# tdlf_08_15_2021_server_top.net
KiCad netlist of a schematic drawn in EAGLE
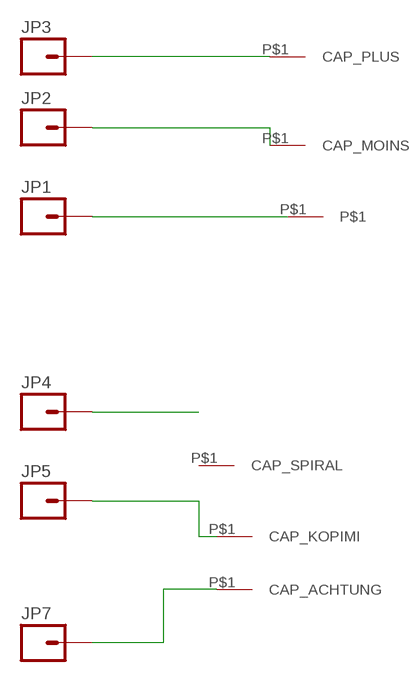
[diagram p0: schematic, sheet 1]

(export (version "E")
  (design (tool "Eeschema 10.0.6"))
  (components
    (comp (ref "CAP_MUSH")
      (value "MUSH")
      (footprint "eagle-import:TDLF_CAP_02")
      (libsource (lib "eagle-import") (part "TDLF_CAP_02"))
    )
    (comp (ref "CAP_PLUS")
      (value "TDLF_CAP_PLUS")
      (footprint "eagle-import:TDLF_CAP_PLUS")
      (libsource (lib "eagle-import") (part "TDLF_CAP_PLUS"))
    )
    (comp (ref "JP1")
      (value "M01SMD")
      (footprint "eagle-import:LUXEON-PAD")
      (libsource (lib "eagle-import") (part "M01SMD"))
    )
    (comp (ref "JP2")
      (value "M01SMD")
      (footprint "eagle-import:LUXEON-PAD")
      (libsource (lib "eagle-import") (part "M01SMD"))
    )
    (comp (ref "JP3")
      (value "M01SMD")
      (footprint "eagle-import:LUXEON-PAD")
      (libsource (lib "eagle-import") (part "M01SMD"))
    )
    (comp (ref "JP4")
      (value "M01SMD")
      (footprint "eagle-import:LUXEON-PAD")
      (libsource (lib "eagle-import") (part "M01SMD"))
    )
    (comp (ref "JP5")
      (value "M01SMD")
      (footprint "eagle-import:LUXEON-PAD")
      (libsource (lib "eagle-import") (part "M01SMD"))
    )
    (comp (ref "JP7")
      (value "M01SMD")
      (footprint "eagle-import:LUXEON-PAD")
      (libsource (lib "eagle-import") (part "M01SMD"))
    )
    (comp (ref "U$1")
      (value "TDLF_CAP_MOINS")
      (footprint "eagle-import:TDLF_CAP_MOINS")
      (libsource (lib "eagle-import") (part "TDLF_CAP_MOINS"))
    )
    (comp (ref "U$2")
      (value "TDLF_CAP_SPIRAL")
      (footprint "eagle-import:TDLF_CAP_SPIRAL")
      (libsource (lib "eagle-import") (part "TDLF_CAP_SPIRAL"))
    )
    (comp (ref "U$3")
      (value "TDLF_CAP_KOPIMI")
      (footprint "eagle-import:TDLF_CAP_KOPIMI")
      (libsource (lib "eagle-import") (part "TDLF_CAP_KOPIMI"))
    )
    (comp (ref "U$4")
      (value "TDLF_CAP_ACHTUNG")
      (footprint "eagle-import:TDLF_CAP_ACHTUNG")
      (libsource (lib "eagle-import") (part "TDLF_CAP_ACHTUNG"))
    )
  )
  (nets
    (net (code "1") (name "Net-(CAP_PLUS-CAP_PLUS)") (class "Default")
      (node (ref "CAP_PLUS") (pin "P$1") (pinfunction "CAP_PLUS_P$1") (pintype "bidirectional"))
      (node (ref "JP3") (pin "P$1") (pinfunction "1_P$1") (pintype "passive"))
    )
    (net (code "2") (name "Net-(JP1-1)") (class "Default")
      (node (ref "CAP_MUSH") (pin "P$1") (pinfunction "P$1_P$1") (pintype "bidirectional"))
      (node (ref "JP1") (pin "P$1") (pinfunction "1_P$1") (pintype "passive"))
    )
    (net (code "3") (name "Net-(JP2-1)") (class "Default")
      (node (ref "JP2") (pin "P$1") (pinfunction "1_P$1") (pintype "passive"))
      (node (ref "U$1") (pin "P$1") (pinfunction "CAP_MOINS_P$1") (pintype "bidirectional"))
    )
    (net (code "4") (name "Net-(JP5-1)") (class "Default")
      (node (ref "JP5") (pin "P$1") (pinfunction "1_P$1") (pintype "passive"))
      (node (ref "U$3") (pin "P$1") (pinfunction "CAP_KOPIMI_P$1") (pintype "bidirectional"))
    )
    (net (code "5") (name "Net-(JP7-1)") (class "Default")
      (node (ref "JP7") (pin "P$1") (pinfunction "1_P$1") (pintype "passive"))
      (node (ref "U$4") (pin "P$1") (pinfunction "CAP_ACHTUNG_P$1") (pintype "bidirectional"))
    )
    (net (code "6") (name "unconnected-(JP4-1-PadP$1)") (class "Default")
      (node (ref "JP4") (pin "P$1") (pinfunction "1_P$1") (pintype "passive"))
    )
    (net (code "7") (name "unconnected-(U$2-CAP_SPIRAL-PadP$1)") (class "Default")
      (node (ref "U$2") (pin "P$1") (pinfunction "CAP_SPIRAL_P$1") (pintype "bidirectional"))
    )
  )
)
